# attiny_programmer.net
KiCad netlist of a schematic drawn in EAGLE
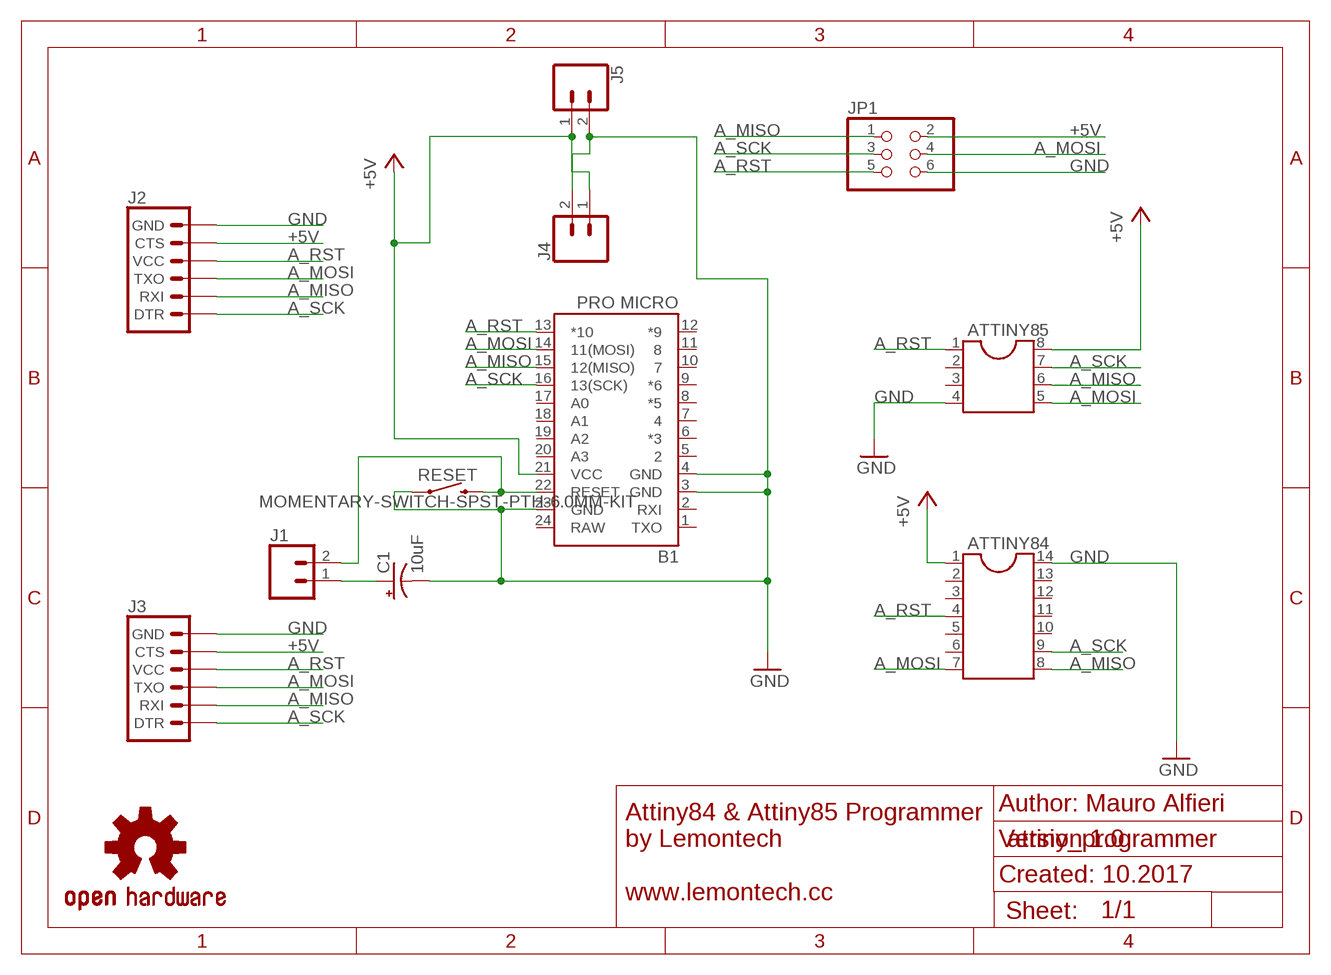
[diagram p0: schematic, sheet 1]

(export (version "E")
  (design (tool "Eeschema 10.0.6"))
  (components
    (comp (ref "ATTINY84")
      (value "DIL14S")
      (footprint "eagle-import:SOCKET-14")
      (libsource (lib "eagle-import") (part "DIL14S"))
    )
    (comp (ref "ATTINY85")
      (value "DIL8S")
      (footprint "eagle-import:SOCKET-08")
      (libsource (lib "eagle-import") (part "DIL8S"))
    )
    (comp (ref "B1")
      (value "PRO MICRO")
      (footprint "eagle-import:SPARKFUN_PRO_MICRO")
      (libsource (lib "eagle-import") (part "SPARKFUN_PRO_MICRO"))
    )
    (comp (ref "C1")
      (value "10uF")
      (footprint "eagle-import:CPOL-RADIAL-2.5MM-5MM")
      (libsource (lib "eagle-import") (part "10UF-POLAR-RADIAL-2.5MM-25V-20%"))
    )
    (comp (ref "J1")
      (value "CONN_02")
      (footprint "eagle-import:1X02")
      (libsource (lib "eagle-import") (part "CONN_02"))
    )
    (comp (ref "J2")
      (value "6_PIN_SERIAL_TARGETLONGPADS")
      (footprint "eagle-import:1X06_LONGPADS")
      (libsource (lib "eagle-import") (part "6_PIN_SERIAL_TARGETLONGPADS"))
    )
    (comp (ref "J3")
      (value "6_PIN_SERIAL_TARGETLONGPADS")
      (footprint "eagle-import:1X06_LONGPADS")
      (libsource (lib "eagle-import") (part "6_PIN_SERIAL_TARGETLONGPADS"))
    )
    (comp (ref "J4")
      (value "CONN_02")
      (footprint "eagle-import:1X02")
      (libsource (lib "eagle-import") (part "CONN_02"))
    )
    (comp (ref "J5")
      (value "CONN_02")
      (footprint "eagle-import:1X02")
      (libsource (lib "eagle-import") (part "CONN_02"))
    )
    (comp (ref "JP1")
      (value "PINHD-2X3")
      (footprint "eagle-import:2X03")
      (libsource (lib "eagle-import") (part "PINHD-2X3"))
    )
    (comp (ref "LOGO1")
      (value "OSHW-LOGOMINI")
      (footprint "eagle-import:OSHW-LOGO-MINI")
      (libsource (lib "eagle-import") (part "OSHW-LOGOMINI"))
    )
    (comp (ref "RESET")
      (value "MOMENTARY-SWITCH-SPST-PTH-6.0MM-KIT")
      (footprint "eagle-import:TACTILE_SWITCH_PTH_6.0MM_KIT")
      (libsource (lib "eagle-import") (part "MOMENTARY-SWITCH-SPST-PTH-6.0MM-KIT"))
    )
  )
  (nets
    (net (code "1") (name "+5V") (class "Default")
      (node (ref "ATTINY84") (pin "1") (pinfunction "1_1") (pintype "passive"))
      (node (ref "ATTINY85") (pin "8") (pinfunction "8_8") (pintype "passive"))
      (node (ref "B1") (pin "21") (pinfunction "VCC_21") (pintype "power_in"))
      (node (ref "J2") (pin "5") (pinfunction "CTS_5") (pintype "passive"))
      (node (ref "J3") (pin "5") (pinfunction "CTS_5") (pintype "passive"))
      (node (ref "J4") (pin "1") (pinfunction "1_1") (pintype "passive"))
      (node (ref "J5") (pin "1") (pinfunction "1_1") (pintype "passive"))
      (node (ref "JP1") (pin "2") (pinfunction "2_2") (pintype "passive"))
    )
    (net (code "2") (name "/A_MISO") (class "Default")
      (node (ref "ATTINY84") (pin "8") (pinfunction "8_8") (pintype "passive"))
      (node (ref "ATTINY85") (pin "6") (pinfunction "6_6") (pintype "passive"))
      (node (ref "B1") (pin "15") (pinfunction "12(MISO)_15") (pintype "bidirectional"))
      (node (ref "J2") (pin "2") (pinfunction "RXI_2") (pintype "passive"))
      (node (ref "J3") (pin "2") (pinfunction "RXI_2") (pintype "passive"))
      (node (ref "JP1") (pin "1") (pinfunction "1_1") (pintype "passive"))
    )
    (net (code "3") (name "/A_MOSI") (class "Default")
      (node (ref "ATTINY84") (pin "7") (pinfunction "7_7") (pintype "passive"))
      (node (ref "ATTINY85") (pin "5") (pinfunction "5_5") (pintype "passive"))
      (node (ref "B1") (pin "14") (pinfunction "11(MOSI)_14") (pintype "bidirectional"))
      (node (ref "J2") (pin "3") (pinfunction "TXO_3") (pintype "passive"))
      (node (ref "J3") (pin "3") (pinfunction "TXO_3") (pintype "passive"))
      (node (ref "JP1") (pin "4") (pinfunction "4_4") (pintype "passive"))
    )
    (net (code "4") (name "/A_RST") (class "Default")
      (node (ref "ATTINY84") (pin "4") (pinfunction "4_4") (pintype "passive"))
      (node (ref "ATTINY85") (pin "1") (pinfunction "1_1") (pintype "passive"))
      (node (ref "B1") (pin "13") (pinfunction "*10_13") (pintype "bidirectional"))
      (node (ref "J2") (pin "4") (pinfunction "VCC_4") (pintype "passive"))
      (node (ref "J3") (pin "4") (pinfunction "VCC_4") (pintype "passive"))
      (node (ref "JP1") (pin "5") (pinfunction "5_5") (pintype "passive"))
    )
    (net (code "5") (name "/A_SCK") (class "Default")
      (node (ref "ATTINY84") (pin "9") (pinfunction "9_9") (pintype "passive"))
      (node (ref "ATTINY85") (pin "7") (pinfunction "7_7") (pintype "passive"))
      (node (ref "B1") (pin "16") (pinfunction "13(SCK)_16") (pintype "bidirectional"))
      (node (ref "J2") (pin "1") (pinfunction "DTR_1") (pintype "passive"))
      (node (ref "J3") (pin "1") (pinfunction "DTR_1") (pintype "passive"))
      (node (ref "JP1") (pin "3") (pinfunction "3_3") (pintype "passive"))
    )
    (net (code "6") (name "/RAW") (class "Default")
      (node (ref "B1") (pin "24") (pinfunction "RAW_24") (pintype "power_in"))
    )
    (net (code "7") (name "GND") (class "Default")
      (node (ref "ATTINY84") (pin "14") (pinfunction "14_14") (pintype "passive"))
      (node (ref "ATTINY85") (pin "4") (pinfunction "4_4") (pintype "passive"))
      (node (ref "B1") (pin "23") (pinfunction "GND_23") (pintype "power_in"))
      (node (ref "B1") (pin "3") (pinfunction "GND_3") (pintype "power_in"))
      (node (ref "B1") (pin "4") (pinfunction "GND_4") (pintype "power_in"))
      (node (ref "C1") (pin "2") (pinfunction "-_2") (pintype "passive"))
      (node (ref "J2") (pin "6") (pinfunction "GND_6") (pintype "passive"))
      (node (ref "J3") (pin "6") (pinfunction "GND_6") (pintype "passive"))
      (node (ref "J4") (pin "2") (pinfunction "2_2") (pintype "passive"))
      (node (ref "J5") (pin "2") (pinfunction "2_2") (pintype "passive"))
      (node (ref "JP1") (pin "6") (pinfunction "6_6") (pintype "passive"))
      (node (ref "RESET") (pin "1") (pinfunction "1_1") (pintype "passive"))
    )
    (net (code "8") (name "Net-(B1-RESET)") (class "Default")
      (node (ref "B1") (pin "22") (pinfunction "RESET_22") (pintype "bidirectional"))
      (node (ref "J1") (pin "2") (pinfunction "2_2") (pintype "passive"))
      (node (ref "RESET") (pin "3") (pinfunction "2_3") (pintype "passive"))
    )
    (net (code "9") (name "Net-(C1-+)") (class "Default")
      (node (ref "C1") (pin "1") (pinfunction "+_1") (pintype "passive"))
      (node (ref "J1") (pin "1") (pinfunction "1_1") (pintype "passive"))
    )
    (net (code "10") (name "unconnected-(ATTINY84-Pad2)") (class "Default")
      (node (ref "ATTINY84") (pin "2") (pinfunction "2_2") (pintype "passive"))
    )
    (net (code "11") (name "unconnected-(ATTINY84-Pad3)") (class "Default")
      (node (ref "ATTINY84") (pin "3") (pinfunction "3_3") (pintype "passive"))
    )
    (net (code "12") (name "unconnected-(ATTINY84-Pad5)") (class "Default")
      (node (ref "ATTINY84") (pin "5") (pinfunction "5_5") (pintype "passive"))
    )
    (net (code "13") (name "unconnected-(ATTINY84-Pad6)") (class "Default")
      (node (ref "ATTINY84") (pin "6") (pinfunction "6_6") (pintype "passive"))
    )
    (net (code "14") (name "unconnected-(ATTINY84-Pad10)") (class "Default")
      (node (ref "ATTINY84") (pin "10") (pinfunction "10_10") (pintype "passive"))
    )
    (net (code "15") (name "unconnected-(ATTINY84-Pad11)") (class "Default")
      (node (ref "ATTINY84") (pin "11") (pinfunction "11_11") (pintype "passive"))
    )
    (net (code "16") (name "unconnected-(ATTINY84-Pad12)") (class "Default")
      (node (ref "ATTINY84") (pin "12") (pinfunction "12_12") (pintype "passive"))
    )
    (net (code "17") (name "unconnected-(ATTINY84-Pad13)") (class "Default")
      (node (ref "ATTINY84") (pin "13") (pinfunction "13_13") (pintype "passive"))
    )
    (net (code "18") (name "unconnected-(ATTINY85-Pad2)") (class "Default")
      (node (ref "ATTINY85") (pin "2") (pinfunction "2_2") (pintype "passive"))
    )
    (net (code "19") (name "unconnected-(ATTINY85-Pad3)") (class "Default")
      (node (ref "ATTINY85") (pin "3") (pinfunction "3_3") (pintype "passive"))
    )
    (net (code "20") (name "unconnected-(B1-*3-Pad6)") (class "Default")
      (node (ref "B1") (pin "6") (pinfunction "*3_6") (pintype "bidirectional"))
    )
    (net (code "21") (name "unconnected-(B1-*5-Pad8)") (class "Default")
      (node (ref "B1") (pin "8") (pinfunction "*5_8") (pintype "bidirectional"))
    )
    (net (code "22") (name "unconnected-(B1-*6-Pad9)") (class "Default")
      (node (ref "B1") (pin "9") (pinfunction "*6_9") (pintype "bidirectional"))
    )
    (net (code "23") (name "unconnected-(B1-*9-Pad12)") (class "Default")
      (node (ref "B1") (pin "12") (pinfunction "*9_12") (pintype "bidirectional"))
    )
    (net (code "24") (name "unconnected-(B1-2-Pad5)") (class "Default")
      (node (ref "B1") (pin "5") (pinfunction "2_5") (pintype "bidirectional"))
    )
    (net (code "25") (name "unconnected-(B1-4-Pad7)") (class "Default")
      (node (ref "B1") (pin "7") (pinfunction "4_7") (pintype "bidirectional"))
    )
    (net (code "26") (name "unconnected-(B1-7-Pad10)") (class "Default")
      (node (ref "B1") (pin "10") (pinfunction "7_10") (pintype "bidirectional"))
    )
    (net (code "27") (name "unconnected-(B1-8-Pad11)") (class "Default")
      (node (ref "B1") (pin "11") (pinfunction "8_11") (pintype "bidirectional"))
    )
    (net (code "28") (name "unconnected-(B1-A0-Pad17)") (class "Default")
      (node (ref "B1") (pin "17") (pinfunction "A0_17") (pintype "bidirectional"))
    )
    (net (code "29") (name "unconnected-(B1-A1-Pad18)") (class "Default")
      (node (ref "B1") (pin "18") (pinfunction "A1_18") (pintype "bidirectional"))
    )
    (net (code "30") (name "unconnected-(B1-A2-Pad19)") (class "Default")
      (node (ref "B1") (pin "19") (pinfunction "A2_19") (pintype "bidirectional"))
    )
    (net (code "31") (name "unconnected-(B1-A3-Pad20)") (class "Default")
      (node (ref "B1") (pin "20") (pinfunction "A3_20") (pintype "bidirectional"))
    )
    (net (code "32") (name "unconnected-(B1-RXI-Pad2)") (class "Default")
      (node (ref "B1") (pin "2") (pinfunction "RXI_2") (pintype "bidirectional"))
    )
    (net (code "33") (name "unconnected-(B1-TXO-Pad1)") (class "Default")
      (node (ref "B1") (pin "1") (pinfunction "TXO_1") (pintype "bidirectional"))
    )
  )
)
